# 07_CAN.net
KiCad netlist of a schematic drawn in Altium Designer
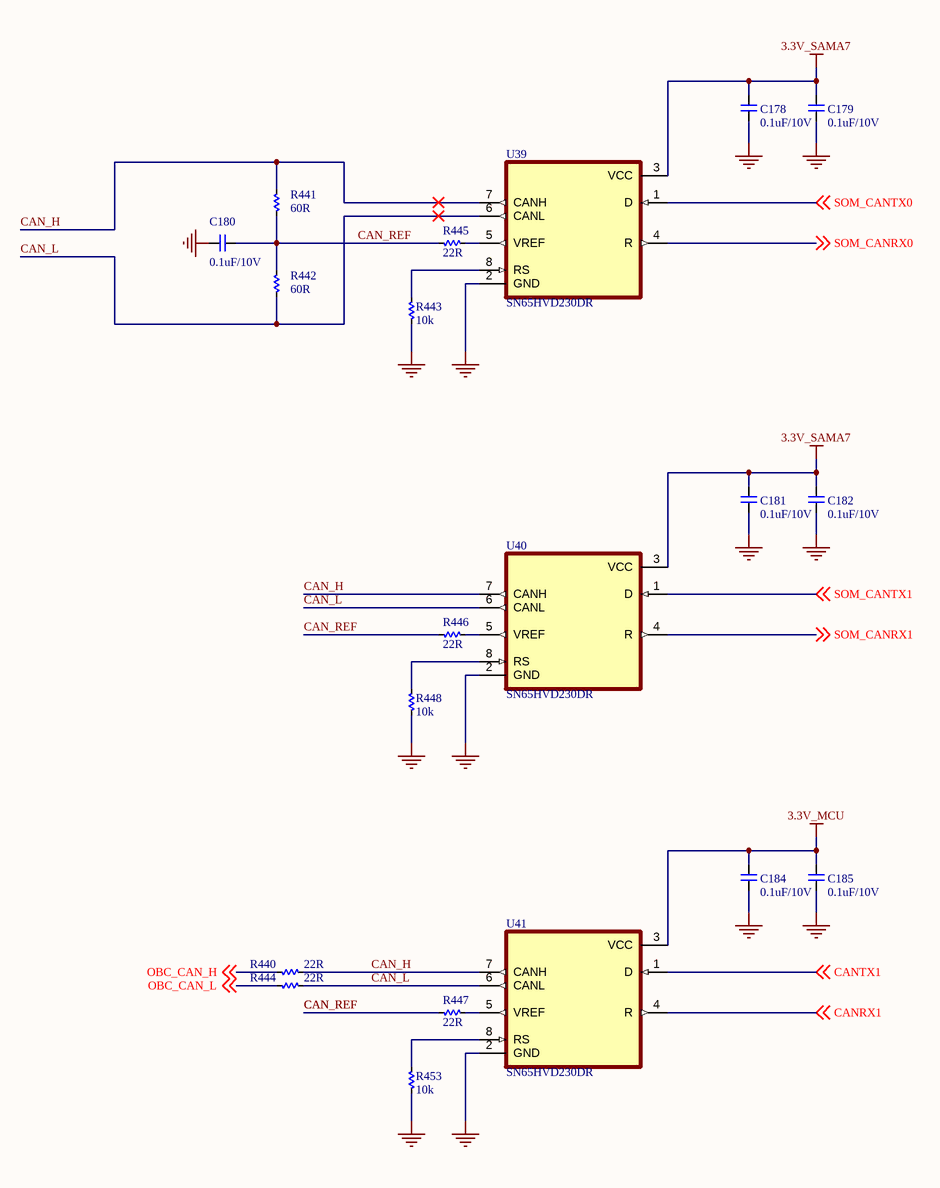
[diagram p0: 07_CAN.SchDoc]

(export (version "E")
  (design (tool "Eeschema 10.0.6"))
  (components
    (comp (ref "C178")
      (value "0.1uF/10V")
      (footprint "CAP_C_1005X50_L")
      (description "CAP")
      (libsource (lib "LABLIB") (part "_CAP_C_2"))
    )
    (comp (ref "C179")
      (value "0.1uF/10V")
      (footprint "CAP_C_1005X50_L")
      (description "CAP")
      (libsource (lib "LABLIB") (part "_CAP_C_2"))
    )
    (comp (ref "C180")
      (value "0.1uF/10V")
      (footprint "CAP_C_1005X50_L")
      (description "CAP")
      (libsource (lib "LABLIB") (part "_CAP_C_2"))
    )
    (comp (ref "C181")
      (value "0.1uF/10V")
      (footprint "CAP_C_1005X50_L")
      (description "CAP")
      (libsource (lib "LABLIB") (part "_CAP_C_2"))
    )
    (comp (ref "C182")
      (value "0.1uF/10V")
      (footprint "CAP_C_1005X50_L")
      (description "CAP")
      (libsource (lib "LABLIB") (part "_CAP_C_2"))
    )
    (comp (ref "C184")
      (value "0.1uF/10V")
      (footprint "CAP_C_1005X50_L")
      (description "CAP")
      (libsource (lib "LABLIB") (part "_CAP_C_2"))
    )
    (comp (ref "C185")
      (value "0.1uF/10V")
      (footprint "CAP_C_1005X50_L")
      (description "CAP")
      (libsource (lib "LABLIB") (part "_CAP_C_2"))
    )
    (comp (ref "R440")
      (value "22R")
      (footprint "RES_C_1005x30_L")
      (description "RES")
      (libsource (lib "LABLIB") (part "_RES_B_2"))
    )
    (comp (ref "R441")
      (value "60R")
      (footprint "RES_C_1005x30_L")
      (description "RES")
      (libsource (lib "LABLIB") (part "_RES_B_2"))
    )
    (comp (ref "R442")
      (value "60R")
      (footprint "RES_C_1005x30_L")
      (description "RES")
      (libsource (lib "LABLIB") (part "_RES_B_2"))
    )
    (comp (ref "R443")
      (value "10k")
      (footprint "RES_C_1005x30_L")
      (description "RES")
      (libsource (lib "LABLIB") (part "_RES_B_2"))
    )
    (comp (ref "R444")
      (value "22R")
      (footprint "RES_C_1005x30_L")
      (description "RES")
      (libsource (lib "LABLIB") (part "_RES_B_2"))
    )
    (comp (ref "R445")
      (value "22R")
      (footprint "RES_C_1005x30_L")
      (description "RES")
      (libsource (lib "LABLIB") (part "_RES_B_2"))
    )
    (comp (ref "R446")
      (value "22R")
      (footprint "RES_C_1005x30_L")
      (description "RES")
      (libsource (lib "LABLIB") (part "_RES_B_2"))
    )
    (comp (ref "R447")
      (value "22R")
      (footprint "RES_C_1005x30_L")
      (description "RES")
      (libsource (lib "LABLIB") (part "_RES_B_2"))
    )
    (comp (ref "R448")
      (value "10k")
      (footprint "RES_C_1005x30_L")
      (description "RES")
      (libsource (lib "LABLIB") (part "_RES_B_2"))
    )
    (comp (ref "R453")
      (value "10k")
      (footprint "RES_C_1005x30_L")
      (description "RES")
      (libsource (lib "LABLIB") (part "_RES_B_2"))
    )
    (comp (ref "U39")
      (value "SN65HVD230DR")
      (footprint "SOIC127P599X175-8N")
      (description "3.3 V CAN Transceiver with Standby Mode")
      (fields (field (name "MF") "Texas Instruments"))
      (libsource (lib "COMM_SCHLIB") (part "SN65HVD230DR"))
    )
    (comp (ref "U40")
      (value "SN65HVD230DR")
      (footprint "SOIC127P599X175-8N")
      (description "3.3 V CAN Transceiver with Standby Mode")
      (fields (field (name "MF") "Texas Instruments"))
      (libsource (lib "COMM_SCHLIB") (part "SN65HVD230DR"))
    )
    (comp (ref "U41")
      (value "SN65HVD230DR")
      (footprint "SOIC127P599X175-8N")
      (description "3.3 V CAN Transceiver with Standby Mode")
      (fields (field (name "MF") "Texas Instruments"))
      (libsource (lib "COMM_SCHLIB") (part "SN65HVD230DR"))
    )
  )
  (nets
    (net (code "1") (name "/CAN_H") (class "Default")
      (node (ref "R440") (pin "2") (pinfunction "2_2") (pintype "passive"))
      (node (ref "R441") (pin "2") (pinfunction "2_2") (pintype "passive"))
      (node (ref "U39") (pin "7") (pinfunction "CANH_7") (pintype "output"))
      (node (ref "U40") (pin "7") (pinfunction "CANH_7") (pintype "output"))
      (node (ref "U41") (pin "7") (pinfunction "CANH_7") (pintype "output"))
    )
    (net (code "2") (name "/CAN_L") (class "Default")
      (node (ref "R442") (pin "1") (pinfunction "1_1") (pintype "passive"))
      (node (ref "R444") (pin "2") (pinfunction "2_2") (pintype "passive"))
      (node (ref "U39") (pin "6") (pinfunction "CANL_6") (pintype "output"))
      (node (ref "U40") (pin "6") (pinfunction "CANL_6") (pintype "output"))
      (node (ref "U41") (pin "6") (pinfunction "CANL_6") (pintype "output"))
    )
    (net (code "3") (name "/CAN_REF") (class "Default")
      (node (ref "C180") (pin "1") (pinfunction "1_1") (pintype "passive"))
      (node (ref "R441") (pin "1") (pinfunction "1_1") (pintype "passive"))
      (node (ref "R442") (pin "2") (pinfunction "2_2") (pintype "passive"))
      (node (ref "R445") (pin "1") (pinfunction "1_1") (pintype "passive"))
      (node (ref "R446") (pin "1") (pinfunction "1_1") (pintype "passive"))
      (node (ref "R447") (pin "1") (pinfunction "1_1") (pintype "passive"))
    )
    (net (code "4") (name "3.3V_MCU") (class "Default")
      (node (ref "C184") (pin "1") (pinfunction "1_1") (pintype "passive"))
      (node (ref "C185") (pin "1") (pinfunction "1_1") (pintype "passive"))
      (node (ref "U41") (pin "3") (pinfunction "VCC_3") (pintype "power_in"))
    )
    (net (code "5") (name "3.3V_SAMA7") (class "Default")
      (node (ref "C178") (pin "1") (pinfunction "1_1") (pintype "passive"))
      (node (ref "C179") (pin "1") (pinfunction "1_1") (pintype "passive"))
      (node (ref "C181") (pin "1") (pinfunction "1_1") (pintype "passive"))
      (node (ref "C182") (pin "1") (pinfunction "1_1") (pintype "passive"))
      (node (ref "U39") (pin "3") (pinfunction "VCC_3") (pintype "power_in"))
      (node (ref "U40") (pin "3") (pinfunction "VCC_3") (pintype "power_in"))
    )
    (net (code "6") (name "CANRX1") (class "Default")
      (node (ref "U41") (pin "4") (pinfunction "R_4") (pintype "output"))
    )
    (net (code "7") (name "CANTX1") (class "Default")
      (node (ref "U41") (pin "1") (pinfunction "D_1") (pintype "input"))
    )
    (net (code "8") (name "GND") (class "Default")
      (node (ref "C178") (pin "2") (pinfunction "2_2") (pintype "passive"))
      (node (ref "C179") (pin "2") (pinfunction "2_2") (pintype "passive"))
      (node (ref "C180") (pin "2") (pinfunction "2_2") (pintype "passive"))
      (node (ref "C181") (pin "2") (pinfunction "2_2") (pintype "passive"))
      (node (ref "C182") (pin "2") (pinfunction "2_2") (pintype "passive"))
      (node (ref "C184") (pin "2") (pinfunction "2_2") (pintype "passive"))
      (node (ref "C185") (pin "2") (pinfunction "2_2") (pintype "passive"))
      (node (ref "R443") (pin "1") (pinfunction "1_1") (pintype "passive"))
      (node (ref "R448") (pin "1") (pinfunction "1_1") (pintype "passive"))
      (node (ref "R453") (pin "1") (pinfunction "1_1") (pintype "passive"))
      (node (ref "U39") (pin "2") (pinfunction "GND_2") (pintype "power_in"))
      (node (ref "U40") (pin "2") (pinfunction "GND_2") (pintype "power_in"))
      (node (ref "U41") (pin "2") (pinfunction "GND_2") (pintype "power_in"))
    )
    (net (code "9") (name "Net-(U39-RS)") (class "Default")
      (node (ref "R443") (pin "2") (pinfunction "2_2") (pintype "passive"))
      (node (ref "U39") (pin "8") (pinfunction "RS_8") (pintype "input"))
    )
    (net (code "10") (name "Net-(U39-VREF)") (class "Default")
      (node (ref "R445") (pin "2") (pinfunction "2_2") (pintype "passive"))
      (node (ref "U39") (pin "5") (pinfunction "VREF_5") (pintype "output"))
    )
    (net (code "11") (name "Net-(U40-RS)") (class "Default")
      (node (ref "R448") (pin "2") (pinfunction "2_2") (pintype "passive"))
      (node (ref "U40") (pin "8") (pinfunction "RS_8") (pintype "input"))
    )
    (net (code "12") (name "Net-(U40-VREF)") (class "Default")
      (node (ref "R446") (pin "2") (pinfunction "2_2") (pintype "passive"))
      (node (ref "U40") (pin "5") (pinfunction "VREF_5") (pintype "output"))
    )
    (net (code "13") (name "Net-(U41-RS)") (class "Default")
      (node (ref "R453") (pin "2") (pinfunction "2_2") (pintype "passive"))
      (node (ref "U41") (pin "8") (pinfunction "RS_8") (pintype "input"))
    )
    (net (code "14") (name "Net-(U41-VREF)") (class "Default")
      (node (ref "R447") (pin "2") (pinfunction "2_2") (pintype "passive"))
      (node (ref "U41") (pin "5") (pinfunction "VREF_5") (pintype "output"))
    )
    (net (code "15") (name "OBC_CAN_H") (class "Default")
      (node (ref "R440") (pin "1") (pinfunction "1_1") (pintype "passive"))
    )
    (net (code "16") (name "OBC_CAN_L") (class "Default")
      (node (ref "R444") (pin "1") (pinfunction "1_1") (pintype "passive"))
    )
    (net (code "17") (name "SOM_CANRX0") (class "Default")
      (node (ref "U39") (pin "4") (pinfunction "R_4") (pintype "output"))
    )
    (net (code "18") (name "SOM_CANRX1") (class "Default")
      (node (ref "U40") (pin "4") (pinfunction "R_4") (pintype "output"))
    )
    (net (code "19") (name "SOM_CANTX0") (class "Default")
      (node (ref "U39") (pin "1") (pinfunction "D_1") (pintype "input"))
    )
    (net (code "20") (name "SOM_CANTX1") (class "Default")
      (node (ref "U40") (pin "1") (pinfunction "D_1") (pintype "input"))
    )
  )
)
